# USB_to_SPI.net
KiCad netlist of a schematic drawn in Altium Designer
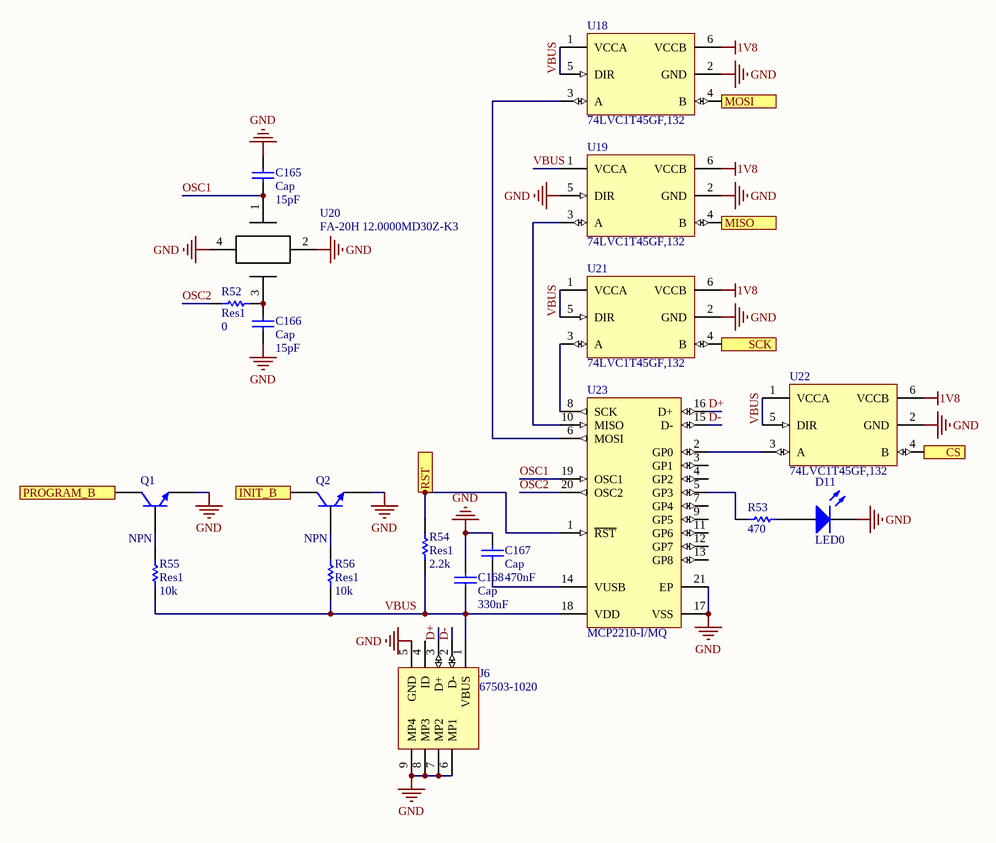
[diagram p0: USB to SPI.SchDoc]

(export (version "E")
  (design (tool "Eeschema 10.0.6"))
  (components
    (comp (ref "C165")
      (value "Cap")
      (footprint "0402-A")
      (description "Capacitor")
      (fields (field (name "ALTIUM_VALUE") "15pF") (field (name "PUBLISHER") "Altium Limited"))
      (libsource (lib "Miscellaneous Devices") (part "Cap"))
    )
    (comp (ref "C166")
      (value "Cap")
      (footprint "0402-A")
      (description "Capacitor")
      (fields (field (name "ALTIUM_VALUE") "15pF") (field (name "PUBLISHER") "Altium Limited"))
      (libsource (lib "Miscellaneous Devices") (part "Cap"))
    )
    (comp (ref "C167")
      (value "Cap")
      (footprint "0402-A")
      (description "Capacitor")
      (fields (field (name "ALTIUM_VALUE") "470nF") (field (name "PUBLISHER") "Altium Limited"))
      (libsource (lib "Miscellaneous Devices") (part "Cap"))
    )
    (comp (ref "C168")
      (value "Cap")
      (footprint "0402-A")
      (description "Capacitor")
      (fields (field (name "ALTIUM_VALUE") "330nF") (field (name "PUBLISHER") "Altium Limited"))
      (libsource (lib "Miscellaneous Devices") (part "Cap"))
    )
    (comp (ref "D11")
      (value "LED0")
      (footprint "1608[0603]")
      (fields (field (name "PUBLISHER") "Altium Limited"))
      (libsource (lib "Miscellaneous Devices") (part "LED0"))
    )
    (comp (ref "J6")
      (value "67503-1020")
      (footprint "MOLX-67503-1020_V")
      (description "USB, MINI, SMD, RA KME04-USBMU03A01")
      (fields (field (name "MANUFACTURER") "Molex"))
      (libsource (lib "Altium Content Vault") (part "MOLX-67503-1020"))
    )
    (comp (ref "Q1")
      (value "NPN")
      (footprint "SOT23_M")
      (description "NPN Bipolar Transistor")
      (fields (field (name "PUBLISHER") "Altium Limited"))
      (libsource (lib "Miscellaneous Devices") (part "NPN"))
    )
    (comp (ref "Q2")
      (value "NPN")
      (footprint "SOT23_M")
      (description "NPN Bipolar Transistor")
      (fields (field (name "PUBLISHER") "Altium Limited"))
      (libsource (lib "Miscellaneous Devices") (part "NPN"))
    )
    (comp (ref "R52")
      (value "Res1")
      (footprint "0402-A")
      (description "Resistor")
      (fields (field (name "ALTIUM_VALUE") "0") (field (name "PUBLISHER") "Altium Limited"))
      (libsource (lib "Miscellaneous Devices") (part "Res1"))
    )
    (comp (ref "R53")
      (value "470")
      (footprint "0402-A")
      (description "Resistor")
      (fields (field (name "Comment") "Res1") (field (name "PUBLISHER") "Altium Limited"))
      (libsource (lib "Miscellaneous Devices") (part "Res1"))
    )
    (comp (ref "R54")
      (value "Res1")
      (footprint "0402-A")
      (description "Resistor")
      (fields (field (name "ALTIUM_VALUE") "2.2k") (field (name "PUBLISHER") "Altium Limited"))
      (libsource (lib "Miscellaneous Devices") (part "Res1"))
    )
    (comp (ref "R55")
      (value "Res1")
      (footprint "0402-A")
      (description "Resistor")
      (fields (field (name "ALTIUM_VALUE") "10k") (field (name "PUBLISHER") "Altium Limited"))
      (libsource (lib "Miscellaneous Devices") (part "Res1"))
    )
    (comp (ref "R56")
      (value "Res1")
      (footprint "0402-A")
      (description "Resistor")
      (fields (field (name "ALTIUM_VALUE") "10k") (field (name "PUBLISHER") "Altium Limited"))
      (libsource (lib "Miscellaneous Devices") (part "Res1"))
    )
    (comp (ref "U18")
      (value "74LVC1T45GF,132")
      (footprint "74LVC1T45GF,132")
      (libsource (lib "74LVC1T45GF,132") (part "74LVC1T45GF,132"))
    )
    (comp (ref "U19")
      (value "74LVC1T45GF,132")
      (footprint "74LVC1T45GF,132")
      (libsource (lib "74LVC1T45GF,132") (part "74LVC1T45GF,132"))
    )
    (comp (ref "U20")
      (value "FA-20H 12.0000MD30Z-K3")
      (footprint "FA-20H 12.0000MD30Z-K3")
      (libsource (lib "XRCGB32M000F1H00R0") (part "XRCGB32M000F1H00R0"))
    )
    (comp (ref "U21")
      (value "74LVC1T45GF,132")
      (footprint "74LVC1T45GF,132")
      (libsource (lib "74LVC1T45GF,132") (part "74LVC1T45GF,132"))
    )
    (comp (ref "U22")
      (value "74LVC1T45GF,132")
      (footprint "74LVC1T45GF,132")
      (libsource (lib "74LVC1T45GF,132") (part "74LVC1T45GF,132"))
    )
    (comp (ref "U23")
      (value "MCP2210-I/MQ")
      (footprint "QFN-MQ20_L")
      (description "USB-to-SPI Protocol Converter with GPIO (Master Mode), 20-Pin QFN, Industrial Temperature")
      (libsource (lib "Altium Content Vault") (part "COM-USB-MCP2210-21"))
    )
  )
  (nets
    (net (code "1") (name "/CS") (class "Default")
      (node (ref "U22") (pin "4") (pinfunction "B_4") (pintype "bidirectional"))
    )
    (net (code "2") (name "/D+") (class "Default")
      (node (ref "J6") (pin "3") (pinfunction "D+_3") (pintype "bidirectional"))
      (node (ref "U23") (pin "16") (pinfunction "D+_16") (pintype "bidirectional"))
    )
    (net (code "3") (name "/D-") (class "Default")
      (node (ref "J6") (pin "2") (pinfunction "D-_2") (pintype "bidirectional"))
      (node (ref "U23") (pin "15") (pinfunction "D-_15") (pintype "bidirectional"))
    )
    (net (code "4") (name "/INIT_B") (class "Default")
      (node (ref "Q2") (pin "1") (pinfunction "C_1") (pintype "passive"))
    )
    (net (code "5") (name "/MISO") (class "Default")
      (node (ref "U19") (pin "4") (pinfunction "B_4") (pintype "bidirectional"))
    )
    (net (code "6") (name "/MOSI") (class "Default")
      (node (ref "U18") (pin "4") (pinfunction "B_4") (pintype "bidirectional"))
    )
    (net (code "7") (name "/OSC1") (class "Default")
      (node (ref "C165") (pin "2") (pinfunction "2_2") (pintype "passive"))
      (node (ref "U20") (pin "1") (pinfunction "1_1") (pintype "passive"))
      (node (ref "U23") (pin "19") (pinfunction "OSC1_19") (pintype "input"))
    )
    (net (code "8") (name "/OSC2") (class "Default")
      (node (ref "R52") (pin "2") (pinfunction "2_2") (pintype "passive"))
      (node (ref "U23") (pin "20") (pinfunction "OSC2_20") (pintype "output"))
    )
    (net (code "9") (name "/PROGRAM_B") (class "Default")
      (node (ref "Q1") (pin "1") (pinfunction "C_1") (pintype "passive"))
    )
    (net (code "10") (name "/RST") (class "Default")
      (node (ref "R54") (pin "2") (pinfunction "2_2") (pintype "passive"))
      (node (ref "U23") (pin "1") (pinfunction "~{RST}_1") (pintype "input"))
    )
    (net (code "11") (name "/SCK") (class "Default")
      (node (ref "U21") (pin "4") (pinfunction "B_4") (pintype "bidirectional"))
    )
    (net (code "12") (name "/VBUS") (class "Default")
      (node (ref "C168") (pin "2") (pinfunction "2_2") (pintype "passive"))
      (node (ref "J6") (pin "1") (pinfunction "VBUS_1") (pintype "power_in"))
      (node (ref "R54") (pin "1") (pinfunction "1_1") (pintype "passive"))
      (node (ref "R55") (pin "1") (pinfunction "1_1") (pintype "passive"))
      (node (ref "R56") (pin "1") (pinfunction "1_1") (pintype "passive"))
      (node (ref "U18") (pin "1") (pinfunction "VCCA_1") (pintype "power_in"))
      (node (ref "U18") (pin "5") (pinfunction "DIR_5") (pintype "input"))
      (node (ref "U19") (pin "1") (pinfunction "VCCA_1") (pintype "power_in"))
      (node (ref "U21") (pin "1") (pinfunction "VCCA_1") (pintype "power_in"))
      (node (ref "U21") (pin "5") (pinfunction "DIR_5") (pintype "input"))
      (node (ref "U22") (pin "1") (pinfunction "VCCA_1") (pintype "power_in"))
      (node (ref "U22") (pin "5") (pinfunction "DIR_5") (pintype "input"))
      (node (ref "U23") (pin "18") (pinfunction "VDD_18") (pintype "power_in"))
    )
    (net (code "13") (name "1V8") (class "Default")
      (node (ref "U18") (pin "6") (pinfunction "VCCB_6") (pintype "power_in"))
      (node (ref "U19") (pin "6") (pinfunction "VCCB_6") (pintype "power_in"))
      (node (ref "U21") (pin "6") (pinfunction "VCCB_6") (pintype "power_in"))
      (node (ref "U22") (pin "6") (pinfunction "VCCB_6") (pintype "power_in"))
    )
    (net (code "14") (name "GND") (class "Default")
      (node (ref "C165") (pin "1") (pinfunction "1_1") (pintype "passive"))
      (node (ref "C166") (pin "2") (pinfunction "2_2") (pintype "passive"))
      (node (ref "C167") (pin "1") (pinfunction "1_1") (pintype "passive"))
      (node (ref "C168") (pin "1") (pinfunction "1_1") (pintype "passive"))
      (node (ref "D11") (pin "2") (pinfunction "K_2") (pintype "passive"))
      (node (ref "J6") (pin "5") (pinfunction "GND_5") (pintype "power_in"))
      (node (ref "J6") (pin "6") (pinfunction "MP1_6") (pintype "passive"))
      (node (ref "J6") (pin "7") (pinfunction "MP2_7") (pintype "passive"))
      (node (ref "J6") (pin "8") (pinfunction "MP3_8") (pintype "passive"))
      (node (ref "J6") (pin "9") (pinfunction "MP4_9") (pintype "passive"))
      (node (ref "Q1") (pin "3") (pinfunction "E_3") (pintype "passive"))
      (node (ref "Q2") (pin "3") (pinfunction "E_3") (pintype "passive"))
      (node (ref "U18") (pin "2") (pinfunction "GND_2") (pintype "power_in"))
      (node (ref "U19") (pin "2") (pinfunction "GND_2") (pintype "power_in"))
      (node (ref "U19") (pin "5") (pinfunction "DIR_5") (pintype "input"))
      (node (ref "U20") (pin "2") (pinfunction "3_2") (pintype "passive"))
      (node (ref "U20") (pin "4") (pinfunction "4_4") (pintype "passive"))
      (node (ref "U21") (pin "2") (pinfunction "GND_2") (pintype "power_in"))
      (node (ref "U22") (pin "2") (pinfunction "GND_2") (pintype "power_in"))
      (node (ref "U23") (pin "17") (pinfunction "VSS_17") (pintype "power_in"))
      (node (ref "U23") (pin "21") (pinfunction "EP_21") (pintype "passive"))
    )
    (net (code "15") (name "Net-(C166-Pad1)") (class "Default")
      (node (ref "C166") (pin "1") (pinfunction "1_1") (pintype "passive"))
      (node (ref "R52") (pin "1") (pinfunction "1_1") (pintype "passive"))
      (node (ref "U20") (pin "3") (pintype "passive"))
    )
    (net (code "16") (name "Net-(D11-A)") (class "Default")
      (node (ref "D11") (pin "1") (pinfunction "A_1") (pintype "passive"))
      (node (ref "R53") (pin "1") (pinfunction "1_1") (pintype "passive"))
    )
    (net (code "17") (name "Net-(Q1-B)") (class "Default")
      (node (ref "Q1") (pin "2") (pinfunction "B_2") (pintype "passive"))
      (node (ref "R55") (pin "2") (pinfunction "2_2") (pintype "passive"))
    )
    (net (code "18") (name "Net-(Q2-B)") (class "Default")
      (node (ref "Q2") (pin "2") (pinfunction "B_2") (pintype "passive"))
      (node (ref "R56") (pin "2") (pinfunction "2_2") (pintype "passive"))
    )
    (net (code "19") (name "Net-(U18-A)") (class "Default")
      (node (ref "U18") (pin "3") (pinfunction "A_3") (pintype "bidirectional"))
      (node (ref "U23") (pin "6") (pinfunction "MOSI_6") (pintype "output"))
    )
    (net (code "20") (name "Net-(U19-A)") (class "Default")
      (node (ref "U19") (pin "3") (pinfunction "A_3") (pintype "bidirectional"))
      (node (ref "U23") (pin "10") (pinfunction "MISO_10") (pintype "input"))
    )
    (net (code "21") (name "Net-(U21-A)") (class "Default")
      (node (ref "U21") (pin "3") (pinfunction "A_3") (pintype "bidirectional"))
      (node (ref "U23") (pin "8") (pinfunction "SCK_8") (pintype "output"))
    )
    (net (code "22") (name "Net-(U22-A)") (class "Default")
      (node (ref "U22") (pin "3") (pinfunction "A_3") (pintype "bidirectional"))
      (node (ref "U23") (pin "2") (pinfunction "GP0_2") (pintype "bidirectional"))
    )
    (net (code "23") (name "Net-(U23-GP3)") (class "Default")
      (node (ref "R53") (pin "2") (pinfunction "2_2") (pintype "passive"))
      (node (ref "U23") (pin "5") (pinfunction "GP3_5") (pintype "bidirectional"))
    )
    (net (code "24") (name "Net-(U23-VUSB)") (class "Default")
      (node (ref "C167") (pin "2") (pinfunction "2_2") (pintype "passive"))
      (node (ref "U23") (pin "14") (pinfunction "VUSB_14") (pintype "power_in"))
    )
    (net (code "25") (name "unconnected-(J6-ID-Pad4)") (class "Default")
      (node (ref "J6") (pin "4") (pinfunction "ID_4") (pintype "passive"))
    )
    (net (code "26") (name "unconnected-(U23-GP1-Pad3)") (class "Default")
      (node (ref "U23") (pin "3") (pinfunction "GP1_3") (pintype "bidirectional"))
    )
    (net (code "27") (name "unconnected-(U23-GP2-Pad4)") (class "Default")
      (node (ref "U23") (pin "4") (pinfunction "GP2_4") (pintype "bidirectional"))
    )
    (net (code "28") (name "unconnected-(U23-GP4-Pad7)") (class "Default")
      (node (ref "U23") (pin "7") (pinfunction "GP4_7") (pintype "bidirectional"))
    )
    (net (code "29") (name "unconnected-(U23-GP5-Pad9)") (class "Default")
      (node (ref "U23") (pin "9") (pinfunction "GP5_9") (pintype "bidirectional"))
    )
    (net (code "30") (name "unconnected-(U23-GP6-Pad11)") (class "Default")
      (node (ref "U23") (pin "11") (pinfunction "GP6_11") (pintype "bidirectional"))
    )
    (net (code "31") (name "unconnected-(U23-GP7-Pad12)") (class "Default")
      (node (ref "U23") (pin "12") (pinfunction "GP7_12") (pintype "bidirectional"))
    )
    (net (code "32") (name "unconnected-(U23-GP8-Pad13)") (class "Default")
      (node (ref "U23") (pin "13") (pinfunction "GP8_13") (pintype "bidirectional"))
    )
  )
)
